# as5047u.net
KiCad netlist of a schematic drawn in Altium Designer
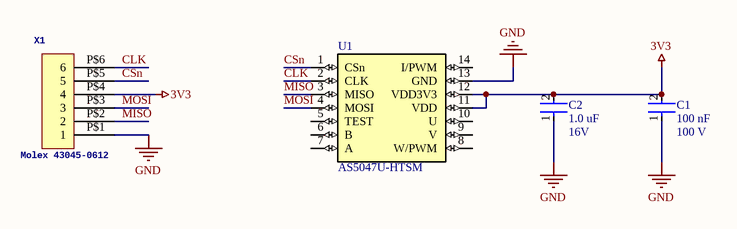
[diagram p0: as5047u.SchDoc]

(export (version "E")
  (design (tool "Eeschema 10.0.6"))
  (components
    (comp (ref "C1")
      (value "CC0603KRX7R0BB104")
      (footprint "CAP-0603")
      (description "CAP CER 0.1UF 100V X7R 0603")
      (fields (field (name "CAPACITANCE") "100 nF") (field (name "VOLTAGE") "100 V"))
      (libsource (lib "JLC_25") (part "CAP-100N-0001"))
    )
    (comp (ref "C2")
      (value "CC0603KRX7R7BB105")
      (footprint "CAP-0603")
      (description "CAP CER 1UF 16V X7R 0603")
      (fields (field (name "CAPACITANCE") "1.0 uF") (field (name "VOLTAGE") "16V"))
      (libsource (lib "JLC_25") (part "CAP-1U-0002"))
    )
    (comp (ref "U1")
      (value "AS5047U-HTSM")
      (footprint "SOP65P640X110-14N")
      (description "Hall Effect Sensor Rotary Position External Magnet, Not Included Gull Wing")
      (fields (field (name "MF") "ams") (field (name "MP") "AS5047D-ATSM"))
      (libsource (lib "MasterLib") (part "IC-ABSENC-0001"))
    )
    (comp (ref "X1")
      (value "Molex 43045-0612")
      (footprint "43045-0612")
      (libsource (lib "Molex Microfit") (part "Micro-Fit Molex 6 Pin 2 Row Vertical"))
    )
  )
  (nets
    (net (code "1") (name "/CLK") (class "Default")
      (node (ref "U1") (pin "2") (pinfunction "CLK_2") (pintype "bidirectional"))
      (node (ref "X1") (pin "P$6") (pinfunction "6_P$6") (pintype "passive"))
    )
    (net (code "2") (name "/CSn") (class "Default")
      (node (ref "U1") (pin "1") (pinfunction "CSn_1") (pintype "bidirectional"))
      (node (ref "X1") (pin "P$5") (pinfunction "5_P$5") (pintype "passive"))
    )
    (net (code "3") (name "/MISO") (class "Default")
      (node (ref "U1") (pin "3") (pinfunction "MISO_3") (pintype "bidirectional"))
      (node (ref "X1") (pin "P$2") (pinfunction "2_P$2") (pintype "passive"))
    )
    (net (code "4") (name "/MOSI") (class "Default")
      (node (ref "U1") (pin "4") (pinfunction "MOSI_4") (pintype "bidirectional"))
      (node (ref "X1") (pin "P$3") (pinfunction "3_P$3") (pintype "passive"))
    )
    (net (code "5") (name "3V3") (class "Default")
      (node (ref "C1") (pin "2") (pinfunction "2_2") (pintype "passive"))
      (node (ref "C2") (pin "2") (pinfunction "2_2") (pintype "passive"))
      (node (ref "U1") (pin "11") (pinfunction "VDD_11") (pintype "bidirectional"))
      (node (ref "U1") (pin "12") (pinfunction "VDD3V3_12") (pintype "bidirectional"))
      (node (ref "X1") (pin "P$4") (pinfunction "4_P$4") (pintype "passive"))
    )
    (net (code "6") (name "GND") (class "Default")
      (node (ref "C1") (pin "1") (pinfunction "1_1") (pintype "passive"))
      (node (ref "C2") (pin "1") (pinfunction "1_1") (pintype "passive"))
      (node (ref "U1") (pin "13") (pinfunction "GND_13") (pintype "bidirectional"))
      (node (ref "X1") (pin "P$1") (pinfunction "1_P$1") (pintype "passive"))
    )
    (net (code "7") (name "unconnected-(U1-A-Pad7)") (class "Default")
      (node (ref "U1") (pin "7") (pinfunction "A_7") (pintype "bidirectional"))
    )
    (net (code "8") (name "unconnected-(U1-B-Pad6)") (class "Default")
      (node (ref "U1") (pin "6") (pinfunction "B_6") (pintype "bidirectional"))
    )
    (net (code "9") (name "unconnected-(U1-I{slash}PWM-Pad14)") (class "Default")
      (node (ref "U1") (pin "14") (pinfunction "I/PWM_14") (pintype "bidirectional"))
    )
    (net (code "10") (name "unconnected-(U1-TEST-Pad5)") (class "Default")
      (node (ref "U1") (pin "5") (pinfunction "TEST_5") (pintype "bidirectional"))
    )
    (net (code "11") (name "unconnected-(U1-U-Pad10)") (class "Default")
      (node (ref "U1") (pin "10") (pinfunction "U_10") (pintype "bidirectional"))
    )
    (net (code "12") (name "unconnected-(U1-V-Pad9)") (class "Default")
      (node (ref "U1") (pin "9") (pinfunction "V_9") (pintype "bidirectional"))
    )
    (net (code "13") (name "unconnected-(U1-W{slash}PWM-Pad8)") (class "Default")
      (node (ref "U1") (pin "8") (pinfunction "W/PWM_8") (pintype "bidirectional"))
    )
  )
)
